# wio_shield.net
KiCad netlist of a schematic drawn in EAGLE
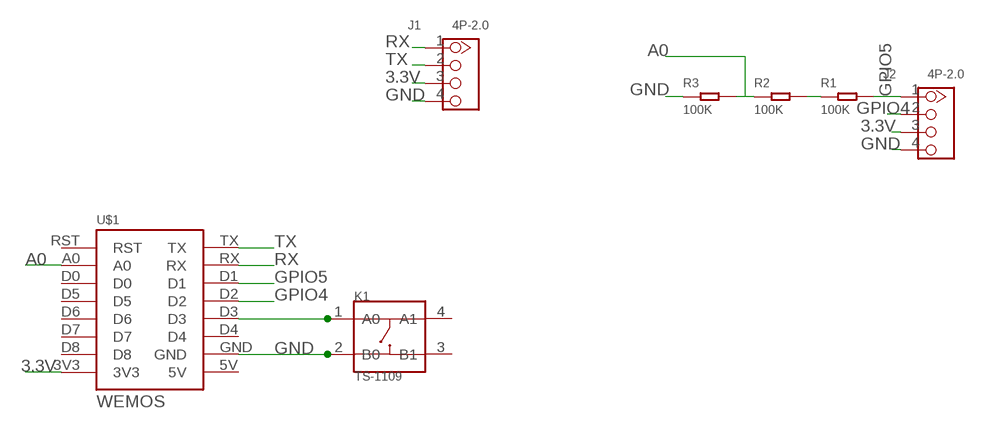
[diagram p0: schematic, sheet 1]

(export (version "E")
  (design (tool "Eeschema 10.0.6"))
  (components
    (comp (ref "J1")
      (value "4P-2.0")
      (footprint "eagle-import:HW4-2.0")
      (libsource (lib "eagle-import") (part "GROVE-CONNECTOR-DIP(4P-2.0)"))
    )
    (comp (ref "J2")
      (value "4P-2.0")
      (footprint "eagle-import:HW4-2.0")
      (libsource (lib "eagle-import") (part "GROVE-CONNECTOR-DIP(4P-2.0)"))
    )
    (comp (ref "K1")
      (value "TS-1109")
      (footprint "eagle-import:SW4-6.0X6.0X5.0MM")
      (libsource (lib "eagle-import") (part "DIP-BUTTON-4P"))
    )
    (comp (ref "R1")
      (value "100K")
      (footprint "eagle-import:PR-D1.8_L3.3MM")
      (fields (field (name "MPN") "FHCFR-1/6W-104J--"))
      (libsource (lib "eagle-import") (part "DIP-RES-100K-5%-1/6W(PR-D1.8XL3.3MM)"))
    )
    (comp (ref "R2")
      (value "100K")
      (footprint "eagle-import:PR-D1.8_L3.3MM")
      (fields (field (name "MPN") "FHCFR-1/6W-104J--"))
      (libsource (lib "eagle-import") (part "DIP-RES-100K-5%-1/6W(PR-D1.8XL3.3MM)"))
    )
    (comp (ref "R3")
      (value "100K")
      (footprint "eagle-import:PR-D1.8_L3.3MM")
      (fields (field (name "MPN") "FHCFR-1/6W-104J--"))
      (libsource (lib "eagle-import") (part "DIP-RES-100K-5%-1/6W(PR-D1.8XL3.3MM)"))
    )
    (comp (ref "U$1")
      (value "WEMOS")
      (footprint "eagle-import:WEMOS")
      (libsource (lib "eagle-import") (part "WEMOS"))
    )
  )
  (nets
    (net (code "1") (name "/3.3V") (class "Default")
      (node (ref "J1") (pin "3") (pinfunction "3_3") (pintype "bidirectional"))
      (node (ref "J2") (pin "3") (pinfunction "3_3") (pintype "bidirectional"))
      (node (ref "U$1") (pin "3V3") (pinfunction "3V3_3V3") (pintype "bidirectional"))
    )
    (net (code "2") (name "/A0") (class "Default")
      (node (ref "R2") (pin "6") (pinfunction "1_6") (pintype "passive"))
      (node (ref "R3") (pin "5") (pinfunction "2_5") (pintype "passive"))
      (node (ref "U$1") (pin "A0") (pinfunction "A0_A0") (pintype "bidirectional"))
    )
    (net (code "3") (name "/GND") (class "Default")
      (node (ref "J1") (pin "4") (pinfunction "4_4") (pintype "bidirectional"))
      (node (ref "J2") (pin "4") (pinfunction "4_4") (pintype "bidirectional"))
      (node (ref "K1") (pin "2") (pinfunction "B0_2") (pintype "bidirectional"))
      (node (ref "R3") (pin "6") (pinfunction "1_6") (pintype "passive"))
      (node (ref "U$1") (pin "GND") (pinfunction "GND_GND") (pintype "bidirectional"))
    )
    (net (code "4") (name "/GPIO4") (class "Default")
      (node (ref "J2") (pin "2") (pinfunction "2_2") (pintype "bidirectional"))
      (node (ref "U$1") (pin "D2") (pinfunction "D2_D2") (pintype "bidirectional"))
    )
    (net (code "5") (name "/GPIO5") (class "Default")
      (node (ref "J2") (pin "1") (pinfunction "1_1") (pintype "bidirectional"))
      (node (ref "R1") (pin "5") (pinfunction "2_5") (pintype "passive"))
      (node (ref "U$1") (pin "D1") (pinfunction "D1_D1") (pintype "bidirectional"))
    )
    (net (code "6") (name "/RX") (class "Default")
      (node (ref "J1") (pin "1") (pinfunction "1_1") (pintype "bidirectional"))
      (node (ref "U$1") (pin "RX") (pinfunction "RX_RX") (pintype "bidirectional"))
    )
    (net (code "7") (name "/TX") (class "Default")
      (node (ref "J1") (pin "2") (pinfunction "2_2") (pintype "bidirectional"))
      (node (ref "U$1") (pin "TX") (pinfunction "TX_TX") (pintype "bidirectional"))
    )
    (net (code "8") (name "Net-(K1-A0)") (class "Default")
      (node (ref "K1") (pin "1") (pinfunction "A0_1") (pintype "bidirectional"))
      (node (ref "U$1") (pin "D3") (pinfunction "D3_D3") (pintype "bidirectional"))
    )
    (net (code "9") (name "Net-(R1-1)") (class "Default")
      (node (ref "R1") (pin "6") (pinfunction "1_6") (pintype "passive"))
      (node (ref "R2") (pin "5") (pinfunction "2_5") (pintype "passive"))
    )
    (net (code "10") (name "unconnected-(K1-A1-Pad4)") (class "Default")
      (node (ref "K1") (pin "4") (pinfunction "A1_4") (pintype "bidirectional"))
    )
    (net (code "11") (name "unconnected-(K1-B1-Pad3)") (class "Default")
      (node (ref "K1") (pin "3") (pinfunction "B1_3") (pintype "bidirectional"))
    )
    (net (code "12") (name "unconnected-(U$1-Pad5V)") (class "Default")
      (node (ref "U$1") (pin "5V") (pinfunction "5V_5V") (pintype "bidirectional"))
    )
    (net (code "13") (name "unconnected-(U$1-PadD0)") (class "Default")
      (node (ref "U$1") (pin "D0") (pinfunction "D0_D0") (pintype "bidirectional"))
    )
    (net (code "14") (name "unconnected-(U$1-PadD4)") (class "Default")
      (node (ref "U$1") (pin "D4") (pinfunction "D4_D4") (pintype "bidirectional"))
    )
    (net (code "15") (name "unconnected-(U$1-PadD5)") (class "Default")
      (node (ref "U$1") (pin "D5") (pinfunction "D5_D5") (pintype "bidirectional"))
    )
    (net (code "16") (name "unconnected-(U$1-PadD6)") (class "Default")
      (node (ref "U$1") (pin "D6") (pinfunction "D6_D6") (pintype "bidirectional"))
    )
    (net (code "17") (name "unconnected-(U$1-PadD7)") (class "Default")
      (node (ref "U$1") (pin "D7") (pinfunction "D7_D7") (pintype "bidirectional"))
    )
    (net (code "18") (name "unconnected-(U$1-PadD8)") (class "Default")
      (node (ref "U$1") (pin "D8") (pinfunction "D8_D8") (pintype "bidirectional"))
    )
    (net (code "19") (name "unconnected-(U$1-PadRST)") (class "Default")
      (node (ref "U$1") (pin "RST") (pinfunction "RST_RST") (pintype "bidirectional"))
    )
  )
)
